# led_board.net
KiCad netlist of a schematic drawn in EAGLE
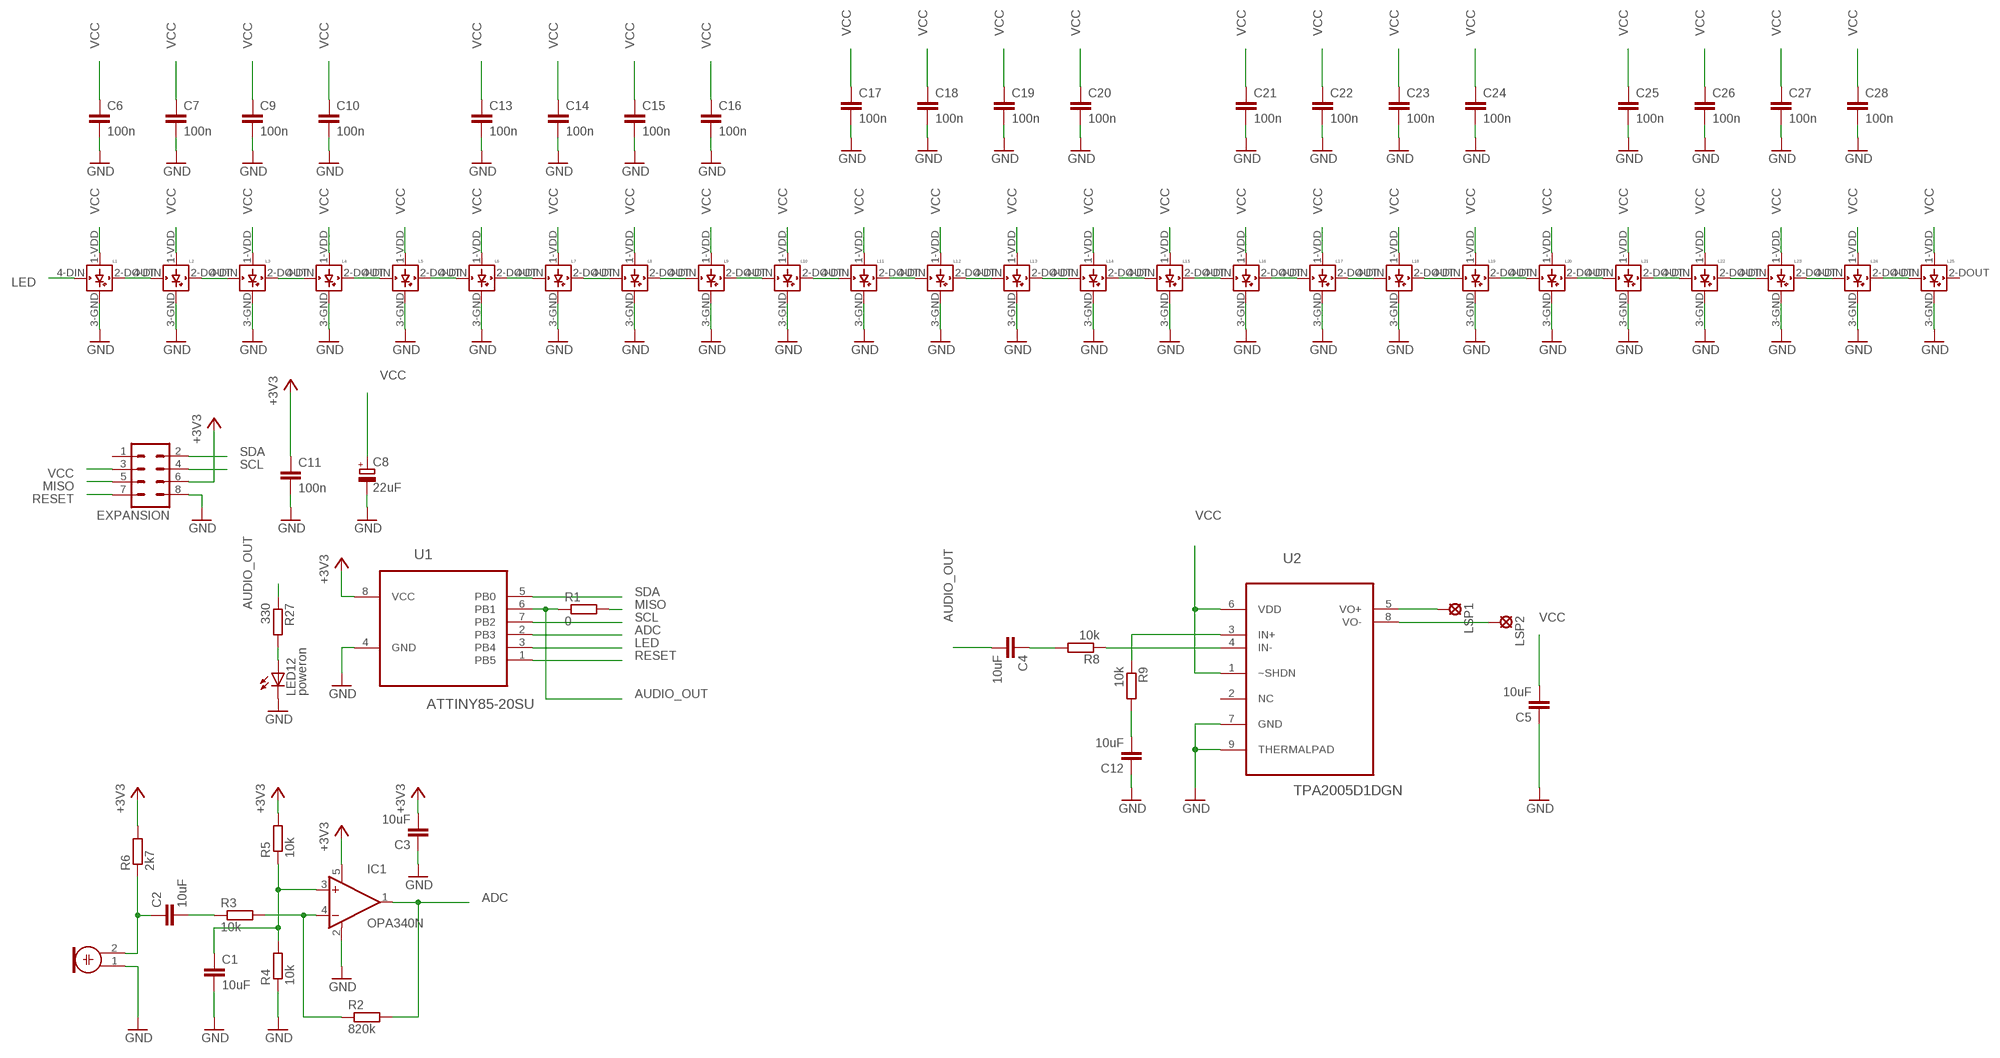
[diagram p0: schematic, sheet 1]

(export (version "E")
  (design (tool "Eeschema 10.0.6"))
  (components
    (comp (ref "C1")
      (value "10uF")
      (footprint "eagle-import:C0805")
      (libsource (lib "eagle-import") (part "C-EUC0805"))
    )
    (comp (ref "C2")
      (value "10uF")
      (footprint "eagle-import:C0805")
      (libsource (lib "eagle-import") (part "C-EUC0805"))
    )
    (comp (ref "C3")
      (value "10uF")
      (footprint "eagle-import:C0805")
      (libsource (lib "eagle-import") (part "C-EUC0805"))
    )
    (comp (ref "C4")
      (value "10uF")
      (footprint "eagle-import:C0805")
      (libsource (lib "eagle-import") (part "C-EUC0805"))
    )
    (comp (ref "C5")
      (value "10uF")
      (footprint "eagle-import:C0805")
      (libsource (lib "eagle-import") (part "C-EUC0805"))
    )
    (comp (ref "C6")
      (value "100n")
      (footprint "eagle-import:C0805")
      (libsource (lib "eagle-import") (part "C-EUC0805"))
    )
    (comp (ref "C7")
      (value "100n")
      (footprint "eagle-import:C0805")
      (libsource (lib "eagle-import") (part "C-EUC0805"))
    )
    (comp (ref "C8")
      (value "22uF")
      (footprint "eagle-import:153CLV-0505")
      (libsource (lib "eagle-import") (part "CPOL-EU153CLV-0505"))
    )
    (comp (ref "C9")
      (value "100n")
      (footprint "eagle-import:C0805")
      (libsource (lib "eagle-import") (part "C-EUC0805"))
    )
    (comp (ref "C10")
      (value "100n")
      (footprint "eagle-import:C0805")
      (libsource (lib "eagle-import") (part "C-EUC0805"))
    )
    (comp (ref "C11")
      (value "100n")
      (footprint "eagle-import:C0805")
      (libsource (lib "eagle-import") (part "C-EUC0805"))
    )
    (comp (ref "C12")
      (value "10uF")
      (footprint "eagle-import:C0805")
      (libsource (lib "eagle-import") (part "C-EUC0805"))
    )
    (comp (ref "C13")
      (value "100n")
      (footprint "eagle-import:C0805")
      (libsource (lib "eagle-import") (part "C-EUC0805"))
    )
    (comp (ref "C14")
      (value "100n")
      (footprint "eagle-import:C0805")
      (libsource (lib "eagle-import") (part "C-EUC0805"))
    )
    (comp (ref "C15")
      (value "100n")
      (footprint "eagle-import:C0805")
      (libsource (lib "eagle-import") (part "C-EUC0805"))
    )
    (comp (ref "C16")
      (value "100n")
      (footprint "eagle-import:C0805")
      (libsource (lib "eagle-import") (part "C-EUC0805"))
    )
    (comp (ref "C17")
      (value "100n")
      (footprint "eagle-import:C0805")
      (libsource (lib "eagle-import") (part "C-EUC0805"))
    )
    (comp (ref "C18")
      (value "100n")
      (footprint "eagle-import:C0805")
      (libsource (lib "eagle-import") (part "C-EUC0805"))
    )
    (comp (ref "C19")
      (value "100n")
      (footprint "eagle-import:C0805")
      (libsource (lib "eagle-import") (part "C-EUC0805"))
    )
    (comp (ref "C20")
      (value "100n")
      (footprint "eagle-import:C0805")
      (libsource (lib "eagle-import") (part "C-EUC0805"))
    )
    (comp (ref "C21")
      (value "100n")
      (footprint "eagle-import:C0805")
      (libsource (lib "eagle-import") (part "C-EUC0805"))
    )
    (comp (ref "C22")
      (value "100n")
      (footprint "eagle-import:C0805")
      (libsource (lib "eagle-import") (part "C-EUC0805"))
    )
    (comp (ref "C23")
      (value "100n")
      (footprint "eagle-import:C0805")
      (libsource (lib "eagle-import") (part "C-EUC0805"))
    )
    (comp (ref "C24")
      (value "100n")
      (footprint "eagle-import:C0805")
      (libsource (lib "eagle-import") (part "C-EUC0805"))
    )
    (comp (ref "C25")
      (value "100n")
      (footprint "eagle-import:C0805")
      (libsource (lib "eagle-import") (part "C-EUC0805"))
    )
    (comp (ref "C26")
      (value "100n")
      (footprint "eagle-import:C0805")
      (libsource (lib "eagle-import") (part "C-EUC0805"))
    )
    (comp (ref "C27")
      (value "100n")
      (footprint "eagle-import:C0805")
      (libsource (lib "eagle-import") (part "C-EUC0805"))
    )
    (comp (ref "C28")
      (value "100n")
      (footprint "eagle-import:C0805")
      (libsource (lib "eagle-import") (part "C-EUC0805"))
    )
    (comp (ref "EXPANSION")
      (value "MA04-2")
      (footprint "eagle-import:MA04-2")
      (libsource (lib "eagle-import") (part "MA04-2"))
    )
    (comp (ref "IC1")
      (value "OPA340N")
      (footprint "eagle-import:SOT23-5")
      (fields (field (name "MPN") "OPA340NA/3KG4"))
      (libsource (lib "eagle-import") (part "OPA340N"))
    )
    (comp (ref "L1")
      (value "WS2812B")
      (footprint "eagle-import:WS2812B")
      (libsource (lib "eagle-import") (part "WS2812B"))
    )
    (comp (ref "L2")
      (value "WS2812B")
      (footprint "eagle-import:WS2812B")
      (libsource (lib "eagle-import") (part "WS2812B"))
    )
    (comp (ref "L3")
      (value "WS2812B")
      (footprint "eagle-import:WS2812B")
      (libsource (lib "eagle-import") (part "WS2812B"))
    )
    (comp (ref "L4")
      (value "WS2812B")
      (footprint "eagle-import:WS2812B")
      (libsource (lib "eagle-import") (part "WS2812B"))
    )
    (comp (ref "L5")
      (value "WS2812B")
      (footprint "eagle-import:WS2812B")
      (libsource (lib "eagle-import") (part "WS2812B"))
    )
    (comp (ref "L6")
      (value "WS2812B")
      (footprint "eagle-import:WS2812B")
      (libsource (lib "eagle-import") (part "WS2812B"))
    )
    (comp (ref "L7")
      (value "WS2812B")
      (footprint "eagle-import:WS2812B")
      (libsource (lib "eagle-import") (part "WS2812B"))
    )
    (comp (ref "L8")
      (value "WS2812B")
      (footprint "eagle-import:WS2812B")
      (libsource (lib "eagle-import") (part "WS2812B"))
    )
    (comp (ref "L9")
      (value "WS2812B")
      (footprint "eagle-import:WS2812B")
      (libsource (lib "eagle-import") (part "WS2812B"))
    )
    (comp (ref "L10")
      (value "WS2812B")
      (footprint "eagle-import:WS2812B")
      (libsource (lib "eagle-import") (part "WS2812B"))
    )
    (comp (ref "L11")
      (value "WS2812B")
      (footprint "eagle-import:WS2812B")
      (libsource (lib "eagle-import") (part "WS2812B"))
    )
    (comp (ref "L12")
      (value "WS2812B")
      (footprint "eagle-import:WS2812B")
      (libsource (lib "eagle-import") (part "WS2812B"))
    )
    (comp (ref "L13")
      (value "WS2812B")
      (footprint "eagle-import:WS2812B")
      (libsource (lib "eagle-import") (part "WS2812B"))
    )
    (comp (ref "L14")
      (value "WS2812B")
      (footprint "eagle-import:WS2812B")
      (libsource (lib "eagle-import") (part "WS2812B"))
    )
    (comp (ref "L15")
      (value "WS2812B")
      (footprint "eagle-import:WS2812B")
      (libsource (lib "eagle-import") (part "WS2812B"))
    )
    (comp (ref "L16")
      (value "WS2812B")
      (footprint "eagle-import:WS2812B")
      (libsource (lib "eagle-import") (part "WS2812B"))
    )
    (comp (ref "L17")
      (value "WS2812B")
      (footprint "eagle-import:WS2812B")
      (libsource (lib "eagle-import") (part "WS2812B"))
    )
    (comp (ref "L18")
      (value "WS2812B")
      (footprint "eagle-import:WS2812B")
      (libsource (lib "eagle-import") (part "WS2812B"))
    )
    (comp (ref "L19")
      (value "WS2812B")
      (footprint "eagle-import:WS2812B")
      (libsource (lib "eagle-import") (part "WS2812B"))
    )
    (comp (ref "L20")
      (value "WS2812B")
      (footprint "eagle-import:WS2812B")
      (libsource (lib "eagle-import") (part "WS2812B"))
    )
    (comp (ref "L21")
      (value "WS2812B")
      (footprint "eagle-import:WS2812B")
      (libsource (lib "eagle-import") (part "WS2812B"))
    )
    (comp (ref "L22")
      (value "WS2812B")
      (footprint "eagle-import:WS2812B")
      (libsource (lib "eagle-import") (part "WS2812B"))
    )
    (comp (ref "L23")
      (value "WS2812B")
      (footprint "eagle-import:WS2812B")
      (libsource (lib "eagle-import") (part "WS2812B"))
    )
    (comp (ref "L24")
      (value "WS2812B")
      (footprint "eagle-import:WS2812B")
      (libsource (lib "eagle-import") (part "WS2812B"))
    )
    (comp (ref "L25")
      (value "WS2812B")
      (footprint "eagle-import:WS2812B")
      (libsource (lib "eagle-import") (part "WS2812B"))
    )
    (comp (ref "LED12")
      (value "poweron")
      (footprint "eagle-import:CHIPLED_1206")
      (libsource (lib "eagle-import") (part "LEDCHIPLED_1206"))
    )
    (comp (ref "LSP1")
      (value "LSP10")
      (footprint "eagle-import:LSP10")
      (libsource (lib "eagle-import") (part "LSP10"))
    )
    (comp (ref "LSP2")
      (value "LSP10")
      (footprint "eagle-import:LSP10")
      (libsource (lib "eagle-import") (part "LSP10"))
    )
    (comp (ref "M1")
      (value "ELECTRET_MICROPHON-WM-61B")
      (footprint "eagle-import:WM-61B")
      (libsource (lib "eagle-import") (part "ELECTRET_MICROPHON-WM-61B"))
    )
    (comp (ref "R1")
      (value "0")
      (footprint "eagle-import:M0805")
      (libsource (lib "eagle-import") (part "R-EU_M0805"))
    )
    (comp (ref "R2")
      (value "820k")
      (footprint "eagle-import:M0805")
      (libsource (lib "eagle-import") (part "R-EU_M0805"))
    )
    (comp (ref "R3")
      (value "10k")
      (footprint "eagle-import:M0805")
      (libsource (lib "eagle-import") (part "R-EU_M0805"))
    )
    (comp (ref "R4")
      (value "10k")
      (footprint "eagle-import:M0805")
      (libsource (lib "eagle-import") (part "R-EU_M0805"))
    )
    (comp (ref "R5")
      (value "10k")
      (footprint "eagle-import:M0805")
      (libsource (lib "eagle-import") (part "R-EU_M0805"))
    )
    (comp (ref "R6")
      (value "2k7")
      (footprint "eagle-import:M0805")
      (libsource (lib "eagle-import") (part "R-EU_M0805"))
    )
    (comp (ref "R8")
      (value "10k")
      (footprint "eagle-import:M0805")
      (libsource (lib "eagle-import") (part "R-EU_M0805"))
    )
    (comp (ref "R9")
      (value "10k")
      (footprint "eagle-import:M0805")
      (libsource (lib "eagle-import") (part "R-EU_M0805"))
    )
    (comp (ref "R27")
      (value "330")
      (footprint "eagle-import:M0805")
      (libsource (lib "eagle-import") (part "R-EU_M0805"))
    )
    (comp (ref "U1")
      (value "ATTINY85-20SU")
      (footprint "eagle-import:SOIC127P798X216-8N")
      (libsource (lib "eagle-import") (part "ATTINY85-20SU"))
    )
    (comp (ref "U2")
      (value "TPA2005D1DGN")
      (footprint "eagle-import:SOP65P488X107-9N")
      (libsource (lib "eagle-import") (part "TPA2005D1DGN"))
    )
  )
  (nets
    (net (code "1") (name "+3V3") (class "Default")
      (node (ref "C11") (pin "1") (pinfunction "1_1") (pintype "passive"))
      (node (ref "C3") (pin "2") (pinfunction "2_2") (pintype "passive"))
      (node (ref "EXPANSION") (pin "6") (pinfunction "6_6") (pintype "passive"))
      (node (ref "IC1") (pin "5") (pinfunction "V+_5") (pintype "power_in"))
      (node (ref "R5") (pin "2") (pinfunction "2_2") (pintype "passive"))
      (node (ref "R6") (pin "2") (pinfunction "2_2") (pintype "passive"))
      (node (ref "U1") (pin "8") (pinfunction "VCC_8") (pintype "power_in"))
    )
    (net (code "2") (name "/ADC") (class "Default")
      (node (ref "IC1") (pin "1") (pinfunction "OUT_1") (pintype "output"))
      (node (ref "R2") (pin "2") (pinfunction "2_2") (pintype "passive"))
      (node (ref "U1") (pin "2") (pinfunction "PB3_2") (pintype "bidirectional"))
    )
    (net (code "3") (name "/AUDIO_OUT") (class "Default")
      (node (ref "C4") (pin "2") (pinfunction "2_2") (pintype "passive"))
      (node (ref "R1") (pin "1") (pinfunction "1_1") (pintype "passive"))
      (node (ref "R27") (pin "1") (pinfunction "1_1") (pintype "passive"))
      (node (ref "U1") (pin "6") (pinfunction "PB1_6") (pintype "bidirectional"))
    )
    (net (code "4") (name "/LED") (class "Default")
      (node (ref "L1") (pin "4-DIN") (pinfunction "DIN_4-DIN") (pintype "input"))
      (node (ref "U1") (pin "3") (pinfunction "PB4_3") (pintype "bidirectional"))
    )
    (net (code "5") (name "/MISO") (class "Default")
      (node (ref "EXPANSION") (pin "5") (pinfunction "5_5") (pintype "passive"))
      (node (ref "R1") (pin "2") (pinfunction "2_2") (pintype "passive"))
    )
    (net (code "6") (name "/RESET") (class "Default")
      (node (ref "EXPANSION") (pin "7") (pinfunction "7_7") (pintype "passive"))
      (node (ref "U1") (pin "1") (pinfunction "PB5_1") (pintype "bidirectional"))
    )
    (net (code "7") (name "/SCL") (class "Default")
      (node (ref "EXPANSION") (pin "4") (pinfunction "4_4") (pintype "passive"))
      (node (ref "U1") (pin "7") (pinfunction "PB2_7") (pintype "bidirectional"))
    )
    (net (code "8") (name "/SDA") (class "Default")
      (node (ref "EXPANSION") (pin "2") (pinfunction "2_2") (pintype "passive"))
      (node (ref "U1") (pin "5") (pinfunction "PB0_5") (pintype "bidirectional"))
    )
    (net (code "9") (name "/VCC") (class "Default")
      (node (ref "C10") (pin "1") (pinfunction "1_1") (pintype "passive"))
      (node (ref "C13") (pin "1") (pinfunction "1_1") (pintype "passive"))
      (node (ref "C14") (pin "1") (pinfunction "1_1") (pintype "passive"))
      (node (ref "C15") (pin "1") (pinfunction "1_1") (pintype "passive"))
      (node (ref "C16") (pin "1") (pinfunction "1_1") (pintype "passive"))
      (node (ref "C17") (pin "1") (pinfunction "1_1") (pintype "passive"))
      (node (ref "C18") (pin "1") (pinfunction "1_1") (pintype "passive"))
      (node (ref "C19") (pin "1") (pinfunction "1_1") (pintype "passive"))
      (node (ref "C20") (pin "1") (pinfunction "1_1") (pintype "passive"))
      (node (ref "C21") (pin "1") (pinfunction "1_1") (pintype "passive"))
      (node (ref "C22") (pin "1") (pinfunction "1_1") (pintype "passive"))
      (node (ref "C23") (pin "1") (pinfunction "1_1") (pintype "passive"))
      (node (ref "C24") (pin "1") (pinfunction "1_1") (pintype "passive"))
      (node (ref "C25") (pin "1") (pinfunction "1_1") (pintype "passive"))
      (node (ref "C26") (pin "1") (pinfunction "1_1") (pintype "passive"))
      (node (ref "C27") (pin "1") (pinfunction "1_1") (pintype "passive"))
      (node (ref "C28") (pin "1") (pinfunction "1_1") (pintype "passive"))
      (node (ref "C5") (pin "2") (pinfunction "2_2") (pintype "passive"))
      (node (ref "C6") (pin "1") (pinfunction "1_1") (pintype "passive"))
      (node (ref "C7") (pin "1") (pinfunction "1_1") (pintype "passive"))
      (node (ref "C8") (pin "+") (pinfunction "+_+") (pintype "passive"))
      (node (ref "C9") (pin "1") (pinfunction "1_1") (pintype "passive"))
      (node (ref "EXPANSION") (pin "3") (pinfunction "3_3") (pintype "passive"))
      (node (ref "L1") (pin "1-VDD") (pinfunction "VDD_1-VDD") (pintype "bidirectional"))
      (node (ref "L10") (pin "1-VDD") (pinfunction "VDD_1-VDD") (pintype "bidirectional"))
      (node (ref "L11") (pin "1-VDD") (pinfunction "VDD_1-VDD") (pintype "bidirectional"))
      (node (ref "L12") (pin "1-VDD") (pinfunction "VDD_1-VDD") (pintype "bidirectional"))
      (node (ref "L13") (pin "1-VDD") (pinfunction "VDD_1-VDD") (pintype "bidirectional"))
      (node (ref "L14") (pin "1-VDD") (pinfunction "VDD_1-VDD") (pintype "bidirectional"))
      (node (ref "L15") (pin "1-VDD") (pinfunction "VDD_1-VDD") (pintype "bidirectional"))
      (node (ref "L16") (pin "1-VDD") (pinfunction "VDD_1-VDD") (pintype "bidirectional"))
      (node (ref "L17") (pin "1-VDD") (pinfunction "VDD_1-VDD") (pintype "bidirectional"))
      (node (ref "L18") (pin "1-VDD") (pinfunction "VDD_1-VDD") (pintype "bidirectional"))
      (node (ref "L19") (pin "1-VDD") (pinfunction "VDD_1-VDD") (pintype "bidirectional"))
      (node (ref "L2") (pin "1-VDD") (pinfunction "VDD_1-VDD") (pintype "bidirectional"))
      (node (ref "L20") (pin "1-VDD") (pinfunction "VDD_1-VDD") (pintype "bidirectional"))
      (node (ref "L21") (pin "1-VDD") (pinfunction "VDD_1-VDD") (pintype "bidirectional"))
      (node (ref "L22") (pin "1-VDD") (pinfunction "VDD_1-VDD") (pintype "bidirectional"))
      (node (ref "L23") (pin "1-VDD") (pinfunction "VDD_1-VDD") (pintype "bidirectional"))
      (node (ref "L24") (pin "1-VDD") (pinfunction "VDD_1-VDD") (pintype "bidirectional"))
      (node (ref "L25") (pin "1-VDD") (pinfunction "VDD_1-VDD") (pintype "bidirectional"))
      (node (ref "L3") (pin "1-VDD") (pinfunction "VDD_1-VDD") (pintype "bidirectional"))
      (node (ref "L4") (pin "1-VDD") (pinfunction "VDD_1-VDD") (pintype "bidirectional"))
      (node (ref "L5") (pin "1-VDD") (pinfunction "VDD_1-VDD") (pintype "bidirectional"))
      (node (ref "L6") (pin "1-VDD") (pinfunction "VDD_1-VDD") (pintype "bidirectional"))
      (node (ref "L7") (pin "1-VDD") (pinfunction "VDD_1-VDD") (pintype "bidirectional"))
      (node (ref "L8") (pin "1-VDD") (pinfunction "VDD_1-VDD") (pintype "bidirectional"))
      (node (ref "L9") (pin "1-VDD") (pinfunction "VDD_1-VDD") (pintype "bidirectional"))
      (node (ref "U2") (pin "1") (pinfunction "~{SHDN}_1") (pintype "passive"))
      (node (ref "U2") (pin "6") (pinfunction "VDD_6") (pintype "power_in"))
    )
    (net (code "10") (name "GND") (class "Default")
      (node (ref "C1") (pin "2") (pinfunction "2_2") (pintype "passive"))
      (node (ref "C10") (pin "2") (pinfunction "2_2") (pintype "passive"))
      (node (ref "C11") (pin "2") (pinfunction "2_2") (pintype "passive"))
      (node (ref "C12") (pin "1") (pinfunction "1_1") (pintype "passive"))
      (node (ref "C13") (pin "2") (pinfunction "2_2") (pintype "passive"))
      (node (ref "C14") (pin "2") (pinfunction "2_2") (pintype "passive"))
      (node (ref "C15") (pin "2") (pinfunction "2_2") (pintype "passive"))
      (node (ref "C16") (pin "2") (pinfunction "2_2") (pintype "passive"))
      (node (ref "C17") (pin "2") (pinfunction "2_2") (pintype "passive"))
      (node (ref "C18") (pin "2") (pinfunction "2_2") (pintype "passive"))
      (node (ref "C19") (pin "2") (pinfunction "2_2") (pintype "passive"))
      (node (ref "C20") (pin "2") (pinfunction "2_2") (pintype "passive"))
      (node (ref "C21") (pin "2") (pinfunction "2_2") (pintype "passive"))
      (node (ref "C22") (pin "2") (pinfunction "2_2") (pintype "passive"))
      (node (ref "C23") (pin "2") (pinfunction "2_2") (pintype "passive"))
      (node (ref "C24") (pin "2") (pinfunction "2_2") (pintype "passive"))
      (node (ref "C25") (pin "2") (pinfunction "2_2") (pintype "passive"))
      (node (ref "C26") (pin "2") (pinfunction "2_2") (pintype "passive"))
      (node (ref "C27") (pin "2") (pinfunction "2_2") (pintype "passive"))
      (node (ref "C28") (pin "2") (pinfunction "2_2") (pintype "passive"))
      (node (ref "C3") (pin "1") (pinfunction "1_1") (pintype "passive"))
      (node (ref "C5") (pin "1") (pinfunction "1_1") (pintype "passive"))
      (node (ref "C6") (pin "2") (pinfunction "2_2") (pintype "passive"))
      (node (ref "C7") (pin "2") (pinfunction "2_2") (pintype "passive"))
      (node (ref "C8") (pin "-") (pinfunction "-_-") (pintype "passive"))
      (node (ref "C9") (pin "2") (pinfunction "2_2") (pintype "passive"))
      (node (ref "EXPANSION") (pin "8") (pinfunction "8_8") (pintype "passive"))
      (node (ref "IC1") (pin "2") (pinfunction "V-_2") (pintype "power_in"))
      (node (ref "L1") (pin "3-GND") (pinfunction "GND_3-GND") (pintype "bidirectional"))
      (node (ref "L10") (pin "3-GND") (pinfunction "GND_3-GND") (pintype "bidirectional"))
      (node (ref "L11") (pin "3-GND") (pinfunction "GND_3-GND") (pintype "bidirectional"))
      (node (ref "L12") (pin "3-GND") (pinfunction "GND_3-GND") (pintype "bidirectional"))
      (node (ref "L13") (pin "3-GND") (pinfunction "GND_3-GND") (pintype "bidirectional"))
      (node (ref "L14") (pin "3-GND") (pinfunction "GND_3-GND") (pintype "bidirectional"))
      (node (ref "L15") (pin "3-GND") (pinfunction "GND_3-GND") (pintype "bidirectional"))
      (node (ref "L16") (pin "3-GND") (pinfunction "GND_3-GND") (pintype "bidirectional"))
      (node (ref "L17") (pin "3-GND") (pinfunction "GND_3-GND") (pintype "bidirectional"))
      (node (ref "L18") (pin "3-GND") (pinfunction "GND_3-GND") (pintype "bidirectional"))
      (node (ref "L19") (pin "3-GND") (pinfunction "GND_3-GND") (pintype "bidirectional"))
      (node (ref "L2") (pin "3-GND") (pinfunction "GND_3-GND") (pintype "bidirectional"))
      (node (ref "L20") (pin "3-GND") (pinfunction "GND_3-GND") (pintype "bidirectional"))
      (node (ref "L21") (pin "3-GND") (pinfunction "GND_3-GND") (pintype "bidirectional"))
      (node (ref "L22") (pin "3-GND") (pinfunction "GND_3-GND") (pintype "bidirectional"))
      (node (ref "L23") (pin "3-GND") (pinfunction "GND_3-GND") (pintype "bidirectional"))
      (node (ref "L24") (pin "3-GND") (pinfunction "GND_3-GND") (pintype "bidirectional"))
      (node (ref "L25") (pin "3-GND") (pinfunction "GND_3-GND") (pintype "bidirectional"))
      (node (ref "L3") (pin "3-GND") (pinfunction "GND_3-GND") (pintype "bidirectional"))
      (node (ref "L4") (pin "3-GND") (pinfunction "GND_3-GND") (pintype "bidirectional"))
      (node (ref "L5") (pin "3-GND") (pinfunction "GND_3-GND") (pintype "bidirectional"))
      (node (ref "L6") (pin "3-GND") (pinfunction "GND_3-GND") (pintype "bidirectional"))
      (node (ref "L7") (pin "3-GND") (pinfunction "GND_3-GND") (pintype "bidirectional"))
      (node (ref "L8") (pin "3-GND") (pinfunction "GND_3-GND") (pintype "bidirectional"))
      (node (ref "L9") (pin "3-GND") (pinfunction "GND_3-GND") (pintype "bidirectional"))
      (node (ref "LED12") (pin "C") (pinfunction "C_C") (pintype "passive"))
      (node (ref "M1") (pin "1") (pinfunction "1_1") (pintype "passive"))
      (node (ref "R4") (pin "1") (pinfunction "1_1") (pintype "passive"))
      (node (ref "U1") (pin "4") (pinfunction "GND_4") (pintype "passive"))
      (node (ref "U2") (pin "7") (pinfunction "GND_7") (pintype "passive"))
      (node (ref "U2") (pin "9") (pinfunction "THERMALPAD_9") (pintype "passive"))
    )
    (net (code "11") (name "Net-(C2-Pad1)") (class "Default")
      (node (ref "C2") (pin "1") (pinfunction "1_1") (pintype "passive"))
      (node (ref "M1") (pin "2") (pinfunction "2_2") (pintype "passive"))
      (node (ref "R6") (pin "1") (pinfunction "1_1") (pintype "passive"))
    )
    (net (code "12") (name "Net-(C2-Pad2)") (class "Default")
      (node (ref "C2") (pin "2") (pinfunction "2_2") (pintype "passive"))
      (node (ref "R3") (pin "1") (pinfunction "1_1") (pintype "passive"))
    )
    (net (code "13") (name "Net-(C4-Pad1)") (class "Default")
      (node (ref "C4") (pin "1") (pinfunction "1_1") (pintype "passive"))
      (node (ref "R8") (pin "2") (pinfunction "2_2") (pintype "passive"))
    )
    (net (code "14") (name "Net-(C12-Pad2)") (class "Default")
      (node (ref "C12") (pin "2") (pinfunction "2_2") (pintype "passive"))
      (node (ref "R9") (pin "2") (pinfunction "2_2") (pintype "passive"))
    )
    (net (code "15") (name "Net-(IC1-+IN)") (class "Default")
      (node (ref "C1") (pin "1") (pinfunction "1_1") (pintype "passive"))
      (node (ref "IC1") (pin "3") (pinfunction "+IN_3") (pintype "input"))
      (node (ref "R4") (pin "2") (pinfunction "2_2") (pintype "passive"))
      (node (ref "R5") (pin "1") (pinfunction "1_1") (pintype "passive"))
    )
    (net (code "16") (name "Net-(IC1--IN)") (class "Default")
      (node (ref "IC1") (pin "4") (pinfunction "-IN_4") (pintype "input"))
      (node (ref "R2") (pin "1") (pinfunction "1_1") (pintype "passive"))
      (node (ref "R3") (pin "2") (pinfunction "2_2") (pintype "passive"))
    )
    (net (code "17") (name "Net-(L1-DOUT)") (class "Default")
      (node (ref "L1") (pin "2-DOUT") (pinfunction "DOUT_2-DOUT") (pintype "output"))
      (node (ref "L2") (pin "4-DIN") (pinfunction "DIN_4-DIN") (pintype "input"))
    )
    (net (code "18") (name "Net-(L2-DOUT)") (class "Default")
      (node (ref "L2") (pin "2-DOUT") (pinfunction "DOUT_2-DOUT") (pintype "output"))
      (node (ref "L3") (pin "4-DIN") (pinfunction "DIN_4-DIN") (pintype "input"))
    )
    (net (code "19") (name "Net-(L3-DOUT)") (class "Default")
      (node (ref "L3") (pin "2-DOUT") (pinfunction "DOUT_2-DOUT") (pintype "output"))
      (node (ref "L4") (pin "4-DIN") (pinfunction "DIN_4-DIN") (pintype "input"))
    )
    (net (code "20") (name "Net-(L4-DOUT)") (class "Default")
      (node (ref "L4") (pin "2-DOUT") (pinfunction "DOUT_2-DOUT") (pintype "output"))
      (node (ref "L5") (pin "4-DIN") (pinfunction "DIN_4-DIN") (pintype "input"))
    )
    (net (code "21") (name "Net-(L5-DOUT)") (class "Default")
      (node (ref "L5") (pin "2-DOUT") (pinfunction "DOUT_2-DOUT") (pintype "output"))
      (node (ref "L6") (pin "4-DIN") (pinfunction "DIN_4-DIN") (pintype "input"))
    )
    (net (code "22") (name "Net-(L6-DOUT)") (class "Default")
      (node (ref "L6") (pin "2-DOUT") (pinfunction "DOUT_2-DOUT") (pintype "output"))
      (node (ref "L7") (pin "4-DIN") (pinfunction "DIN_4-DIN") (pintype "input"))
    )
    (net (code "23") (name "Net-(L7-DOUT)") (class "Default")
      (node (ref "L7") (pin "2-DOUT") (pinfunction "DOUT_2-DOUT") (pintype "output"))
      (node (ref "L8") (pin "4-DIN") (pinfunction "DIN_4-DIN") (pintype "input"))
    )
    (net (code "24") (name "Net-(L8-DOUT)") (class "Default")
      (node (ref "L8") (pin "2-DOUT") (pinfunction "DOUT_2-DOUT") (pintype "output"))
      (node (ref "L9") (pin "4-DIN") (pinfunction "DIN_4-DIN") (pintype "input"))
    )
    (net (code "25") (name "Net-(L10-DIN)") (class "Default")
      (node (ref "L10") (pin "4-DIN") (pinfunction "DIN_4-DIN") (pintype "input"))
      (node (ref "L9") (pin "2-DOUT") (pinfunction "DOUT_2-DOUT") (pintype "output"))
    )
    (net (code "26") (name "Net-(L10-DOUT)") (class "Default")
      (node (ref "L10") (pin "2-DOUT") (pinfunction "DOUT_2-DOUT") (pintype "output"))
      (node (ref "L11") (pin "4-DIN") (pinfunction "DIN_4-DIN") (pintype "input"))
    )
    (net (code "27") (name "Net-(L11-DOUT)") (class "Default")
      (node (ref "L11") (pin "2-DOUT") (pinfunction "DOUT_2-DOUT") (pintype "output"))
      (node (ref "L12") (pin "4-DIN") (pinfunction "DIN_4-DIN") (pintype "input"))
    )
    (net (code "28") (name "Net-(L12-DOUT)") (class "Default")
      (node (ref "L12") (pin "2-DOUT") (pinfunction "DOUT_2-DOUT") (pintype "output"))
      (node (ref "L13") (pin "4-DIN") (pinfunction "DIN_4-DIN") (pintype "input"))
    )
    (net (code "29") (name "Net-(L13-DOUT)") (class "Default")
      (node (ref "L13") (pin "2-DOUT") (pinfunction "DOUT_2-DOUT") (pintype "output"))
      (node (ref "L14") (pin "4-DIN") (pinfunction "DIN_4-DIN") (pintype "input"))
    )
    (net (code "30") (name "Net-(L14-DOUT)") (class "Default")
      (node (ref "L14") (pin "2-DOUT") (pinfunction "DOUT_2-DOUT") (pintype "output"))
      (node (ref "L15") (pin "4-DIN") (pinfunction "DIN_4-DIN") (pintype "input"))
    )
    (net (code "31") (name "Net-(L15-DOUT)") (class "Default")
      (node (ref "L15") (pin "2-DOUT") (pinfunction "DOUT_2-DOUT") (pintype "output"))
      (node (ref "L16") (pin "4-DIN") (pinfunction "DIN_4-DIN") (pintype "input"))
    )
    (net (code "32") (name "Net-(L16-DOUT)") (class "Default")
      (node (ref "L16") (pin "2-DOUT") (pinfunction "DOUT_2-DOUT") (pintype "output"))
      (node (ref "L17") (pin "4-DIN") (pinfunction "DIN_4-DIN") (pintype "input"))
    )
    (net (code "33") (name "Net-(L17-DOUT)") (class "Default")
      (node (ref "L17") (pin "2-DOUT") (pinfunction "DOUT_2-DOUT") (pintype "output"))
      (node (ref "L18") (pin "4-DIN") (pinfunction "DIN_4-DIN") (pintype "input"))
    )
    (net (code "34") (name "Net-(L18-DOUT)") (class "Default")
      (node (ref "L18") (pin "2-DOUT") (pinfunction "DOUT_2-DOUT") (pintype "output"))
      (node (ref "L19") (pin "4-DIN") (pinfunction "DIN_4-DIN") (pintype "input"))
    )
    (net (code "35") (name "Net-(L19-DOUT)") (class "Default")
      (node (ref "L19") (pin "2-DOUT") (pinfunction "DOUT_2-DOUT") (pintype "output"))
      (node (ref "L20") (pin "4-DIN") (pinfunction "DIN_4-DIN") (pintype "input"))
    )
    (net (code "36") (name "Net-(L20-DOUT)") (class "Default")
      (node (ref "L20") (pin "2-DOUT") (pinfunction "DOUT_2-DOUT") (pintype "output"))
      (node (ref "L21") (pin "4-DIN") (pinfunction "DIN_4-DIN") (pintype "input"))
    )
    (net (code "37") (name "Net-(L21-DOUT)") (class "Default")
      (node (ref "L21") (pin "2-DOUT") (pinfunction "DOUT_2-DOUT") (pintype "output"))
      (node (ref "L22") (pin "4-DIN") (pinfunction "DIN_4-DIN") (pintype "input"))
    )
    (net (code "38") (name "Net-(L22-DOUT)") (class "Default")
      (node (ref "L22") (pin "2-DOUT") (pinfunction "DOUT_2-DOUT") (pintype "output"))
      (node (ref "L23") (pin "4-DIN") (pinfunction "DIN_4-DIN") (pintype "input"))
    )
    (net (code "39") (name "Net-(L23-DOUT)") (class "Default")
      (node (ref "L23") (pin "2-DOUT") (pinfunction "DOUT_2-DOUT") (pintype "output"))
      (node (ref "L24") (pin "4-DIN") (pinfunction "DIN_4-DIN") (pintype "input"))
    )
    (net (code "40") (name "Net-(L24-DOUT)") (class "Default")
      (node (ref "L24") (pin "2-DOUT") (pinfunction "DOUT_2-DOUT") (pintype "output"))
      (node (ref "L25") (pin "4-DIN") (pinfunction "DIN_4-DIN") (pintype "input"))
    )
    (net (code "41") (name "Net-(LED12-PadA)") (class "Default")
      (node (ref "LED12") (pin "A") (pinfunction "A_A") (pintype "passive"))
      (node (ref "R27") (pin "2") (pinfunction "2_2") (pintype "passive"))
    )
    (net (code "42") (name "Net-(U2-IN+)") (class "Default")
      (node (ref "R9") (pin "1") (pinfunction "1_1") (pintype "passive"))
      (node (ref "U2") (pin "3") (pinfunction "IN+_3") (pintype "input"))
    )
    (net (code "43") (name "Net-(U2-IN-)") (class "Default")
      (node (ref "R8") (pin "1") (pinfunction "1_1") (pintype "passive"))
      (node (ref "U2") (pin "4") (pinfunction "IN-_4") (pintype "input"))
    )
    (net (code "44") (name "Net-(U2-VO+)") (class "Default")
      (node (ref "LSP1") (pin "MP") (pinfunction "MP_MP") (pintype "passive"))
      (node (ref "U2") (pin "5") (pinfunction "VO+_5") (pintype "output"))
    )
    (net (code "45") (name "Net-(U2-VO-)") (class "Default")
      (node (ref "LSP2") (pin "MP") (pinfunction "MP_MP") (pintype "passive"))
      (node (ref "U2") (pin "8") (pinfunction "VO-_8") (pintype "output"))
    )
    (net (code "46") (name "unconnected-(EXPANSION-Pad1)") (class "Default")
      (node (ref "EXPANSION") (pin "1") (pinfunction "1_1") (pintype "passive"))
    )
    (net (code "47") (name "unconnected-(L25-DOUT-Pad2-DOUT)") (class "Default")
      (node (ref "L25") (pin "2-DOUT") (pinfunction "DOUT_2-DOUT") (pintype "output"))
    )
    (net (code "48") (name "unconnected-(U2-NC-Pad2)") (class "Default")
      (node (ref "U2") (pin "2") (pinfunction "NC_2") (pintype "no_connect"))
    )
  )
)
